# csa_sid_v1_0b.net
KiCad netlist of a schematic drawn in EAGLE
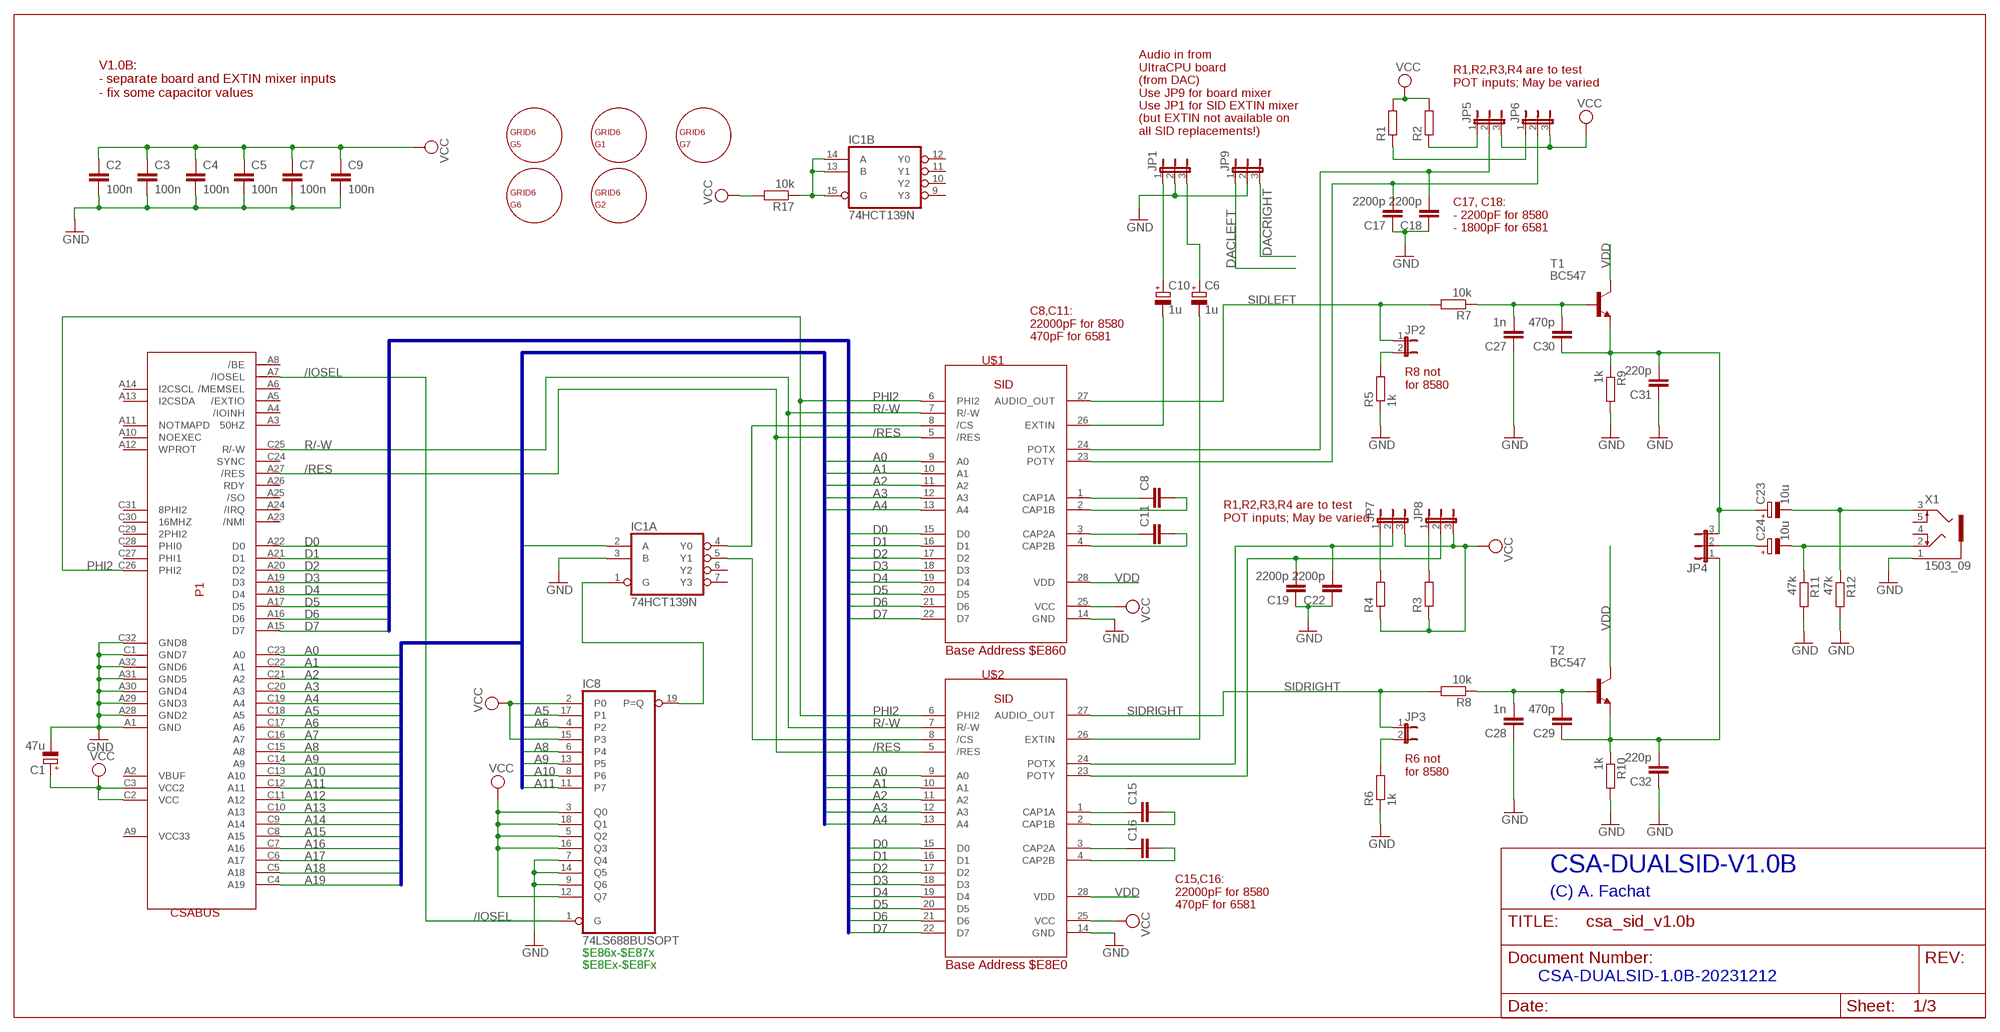
[diagram p0: schematic, sheet 1]
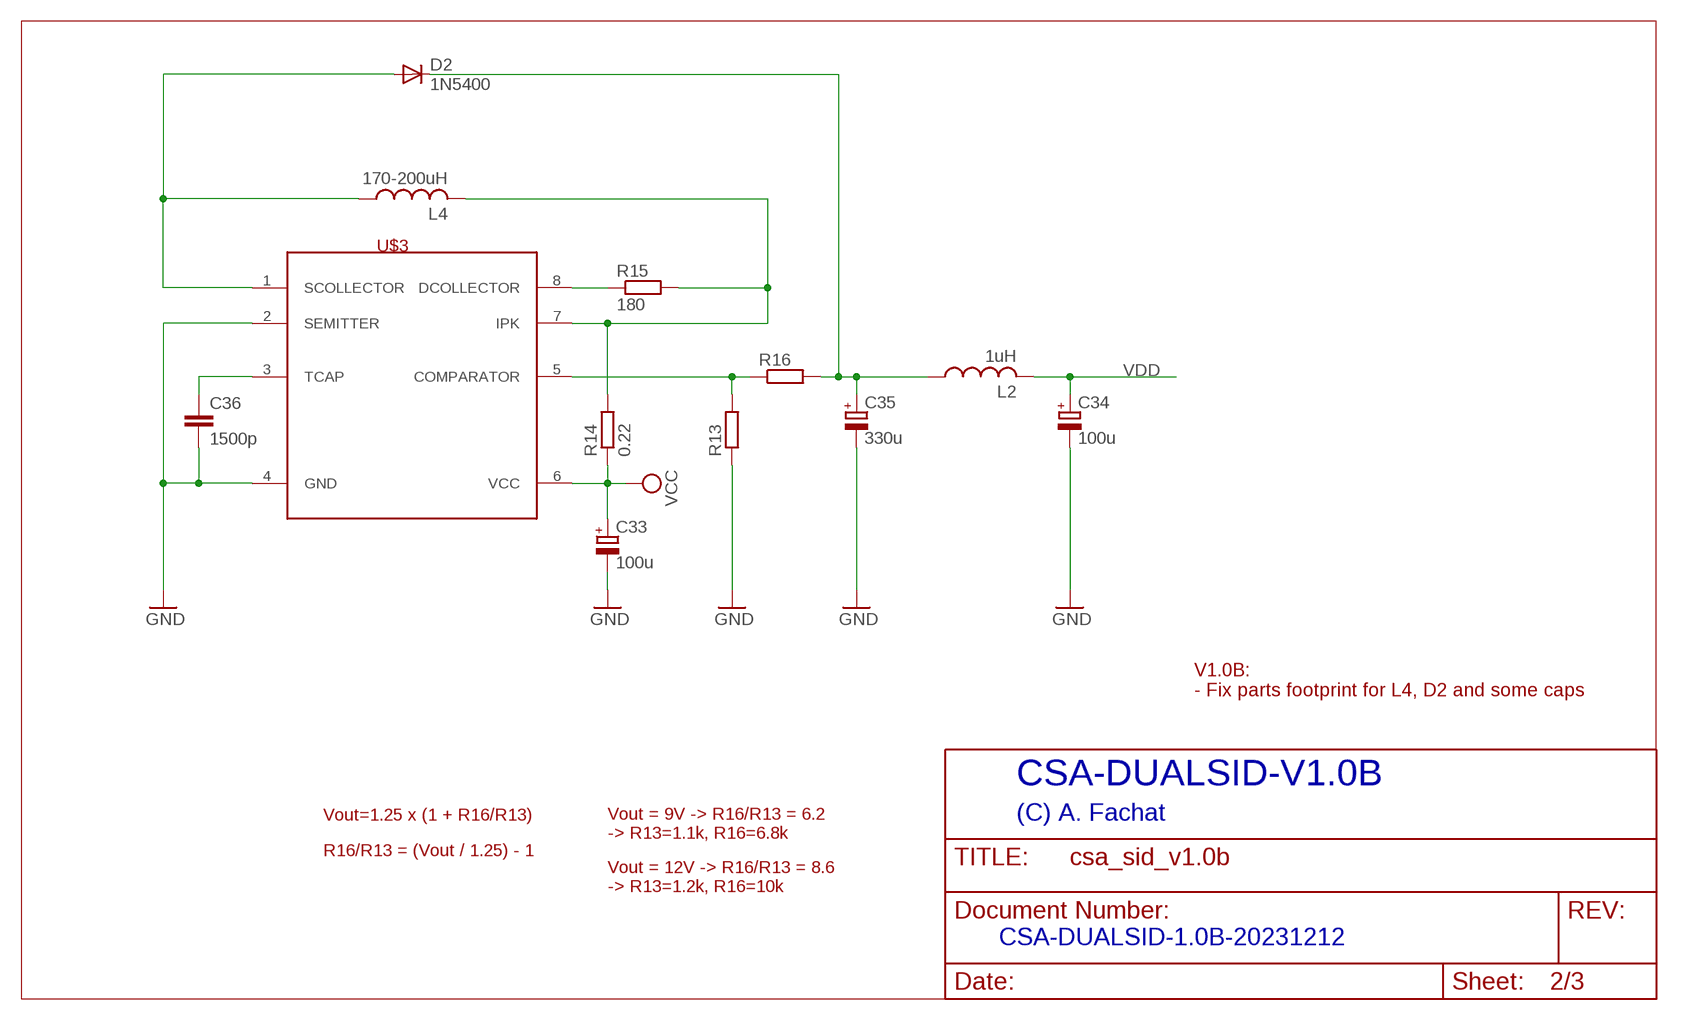
[diagram p1: schematic, sheet 2]
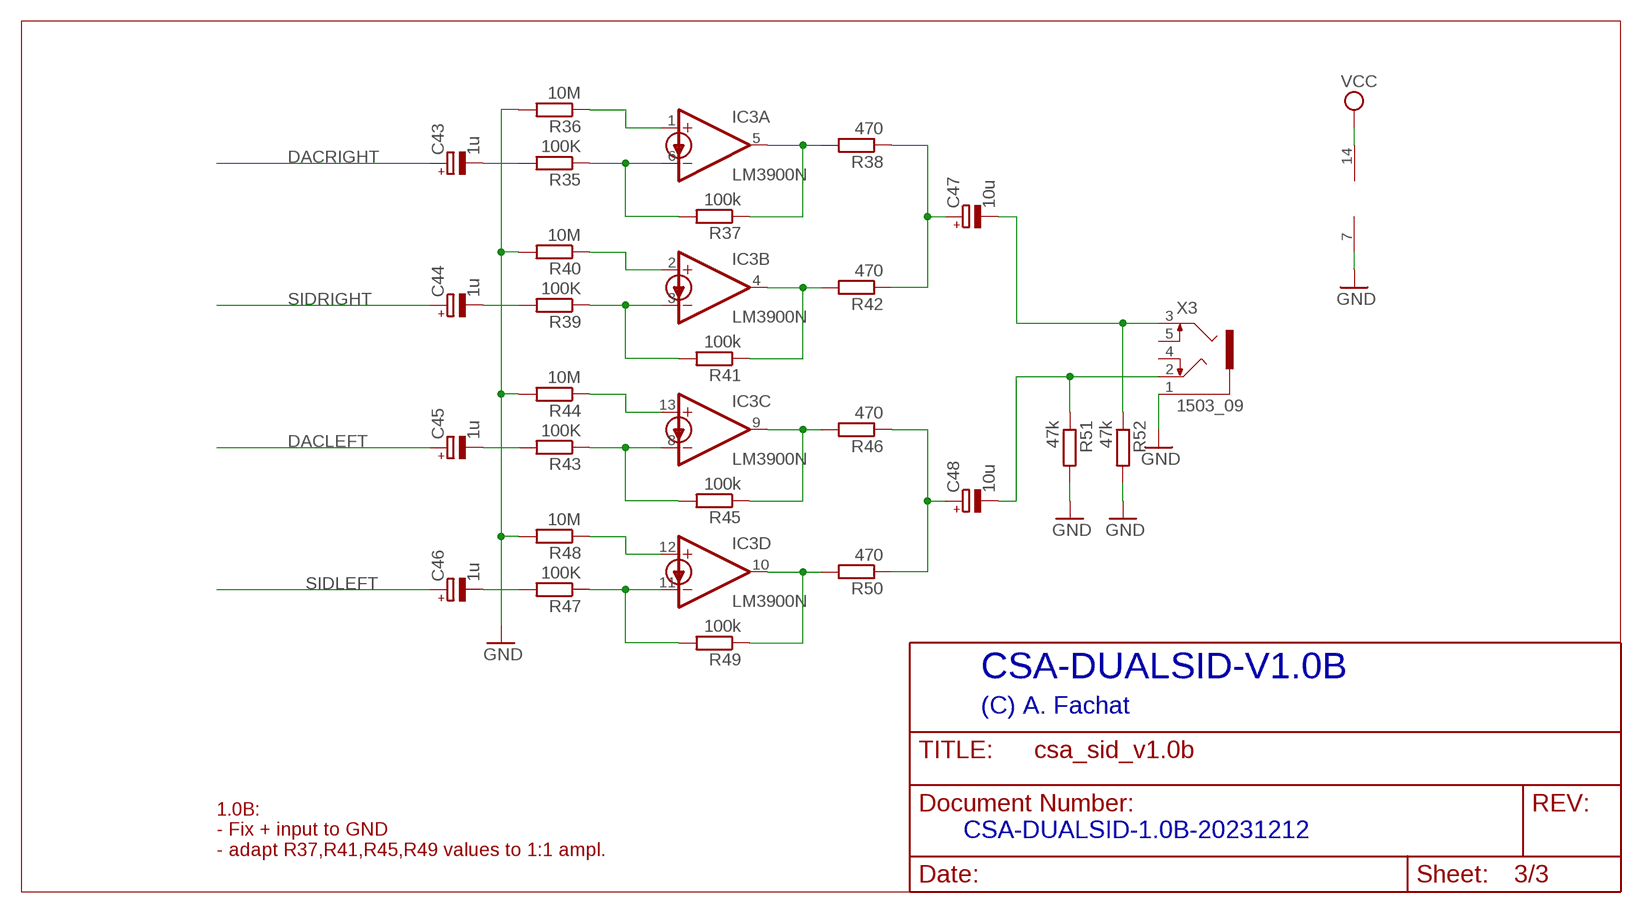
[diagram p2: schematic, sheet 3]

(export (version "E")
  (design (tool "Eeschema 10.0.6"))
  (components
    (comp (ref "C33")
      (value "100u")
      (footprint "eagle-import:E2,5-7")
      (libsource (lib "eagle-import") (part "CPOL-EUE2.5-7"))
    )
    (comp (ref "C34")
      (value "100u")
      (footprint "eagle-import:E2,5-7")
      (libsource (lib "eagle-import") (part "CPOL-EUE2.5-7"))
    )
    (comp (ref "C35")
      (value "330u")
      (footprint "eagle-import:E2,5-7")
      (libsource (lib "eagle-import") (part "CPOL-EUE2.5-7"))
    )
    (comp (ref "C36")
      (value "1500p")
      (footprint "eagle-import:C025-024X044")
      (libsource (lib "eagle-import") (part "C-EU025-024X044"))
    )
    (comp (ref "D2")
      (value "1N5400")
      (footprint "eagle-import:DO201-15")
      (libsource (lib "eagle-import") (part "1N5400"))
    )
    (comp (ref "L2")
      (value "1uH")
      (footprint "eagle-import:0204_7")
      (libsource (lib "eagle-import") (part "L-US0204/7"))
    )
    (comp (ref "L4")
      (value "170-200uH")
      (footprint "eagle-import:TJ4-U2")
      (libsource (lib "eagle-import") (part "L-USTJ4-U2"))
    )
    (comp (ref "R13")
      (value "R-EU_0204/7")
      (footprint "eagle-import:0204_7")
      (libsource (lib "eagle-import") (part "R-EU_0204/7"))
    )
    (comp (ref "R14")
      (value "0.22")
      (footprint "eagle-import:0204_7")
      (libsource (lib "eagle-import") (part "R-EU_0204/7"))
    )
    (comp (ref "R15")
      (value "180")
      (footprint "eagle-import:0204_7")
      (libsource (lib "eagle-import") (part "R-EU_0204/7"))
    )
    (comp (ref "R16")
      (value "R-EU_0204/7")
      (footprint "eagle-import:0204_7")
      (libsource (lib "eagle-import") (part "R-EU_0204/7"))
    )
    (comp (ref "U$3")
      (value "MC34063A")
      (footprint "eagle-import:DIL08")
      (libsource (lib "eagle-import") (part "MC34063A"))
    )
    (comp (ref "C1")
      (value "47u")
      (footprint "eagle-import:E2,5-7")
      (libsource (lib "eagle-import") (part "CPOL-EUE2.5-7"))
    )
    (comp (ref "C2")
      (value "100n")
      (footprint "eagle-import:C025-025X050")
      (libsource (lib "eagle-import") (part "C-EU025-025X050"))
    )
    (comp (ref "C3")
      (value "100n")
      (footprint "eagle-import:C025-025X050")
      (libsource (lib "eagle-import") (part "C-EU025-025X050"))
    )
    (comp (ref "C4")
      (value "100n")
      (footprint "eagle-import:C025-025X050")
      (libsource (lib "eagle-import") (part "C-EU025-025X050"))
    )
    (comp (ref "C5")
      (value "100n")
      (footprint "eagle-import:C025-025X050")
      (libsource (lib "eagle-import") (part "C-EU025-025X050"))
    )
    (comp (ref "C6")
      (value "1u")
      (footprint "eagle-import:E2-5")
      (libsource (lib "eagle-import") (part "CPOL-EUE2-5"))
    )
    (comp (ref "C7")
      (value "100n")
      (footprint "eagle-import:C025-025X050")
      (libsource (lib "eagle-import") (part "C-EU025-025X050"))
    )
    (comp (ref "C8")
      (value "C-EU025-025X050")
      (footprint "eagle-import:C025-025X050")
      (libsource (lib "eagle-import") (part "C-EU025-025X050"))
    )
    (comp (ref "C9")
      (value "100n")
      (footprint "eagle-import:C025-025X050")
      (libsource (lib "eagle-import") (part "C-EU025-025X050"))
    )
    (comp (ref "C10")
      (value "1u")
      (footprint "eagle-import:E2-5")
      (libsource (lib "eagle-import") (part "CPOL-EUE2-5"))
    )
    (comp (ref "C11")
      (value "C-EU025-025X050")
      (footprint "eagle-import:C025-025X050")
      (libsource (lib "eagle-import") (part "C-EU025-025X050"))
    )
    (comp (ref "C15")
      (value "C-EU025-025X050")
      (footprint "eagle-import:C025-025X050")
      (libsource (lib "eagle-import") (part "C-EU025-025X050"))
    )
    (comp (ref "C16")
      (value "C-EU025-025X050")
      (footprint "eagle-import:C025-025X050")
      (libsource (lib "eagle-import") (part "C-EU025-025X050"))
    )
    (comp (ref "C17")
      (value "2200p")
      (footprint "eagle-import:C025-025X050")
      (libsource (lib "eagle-import") (part "C-EU025-025X050"))
    )
    (comp (ref "C18")
      (value "2200p")
      (footprint "eagle-import:C025-025X050")
      (libsource (lib "eagle-import") (part "C-EU025-025X050"))
    )
    (comp (ref "C19")
      (value "2200p")
      (footprint "eagle-import:C025-025X050")
      (libsource (lib "eagle-import") (part "C-EU025-025X050"))
    )
    (comp (ref "C22")
      (value "2200p")
      (footprint "eagle-import:C025-025X050")
      (libsource (lib "eagle-import") (part "C-EU025-025X050"))
    )
    (comp (ref "C23")
      (value "10u")
      (footprint "eagle-import:E2-5")
      (libsource (lib "eagle-import") (part "CPOL-EUE2-5"))
    )
    (comp (ref "C24")
      (value "10u")
      (footprint "eagle-import:E2-5")
      (libsource (lib "eagle-import") (part "CPOL-EUE2-5"))
    )
    (comp (ref "C27")
      (value "1n")
      (footprint "eagle-import:C025-025X050")
      (libsource (lib "eagle-import") (part "C-EU025-025X050"))
    )
    (comp (ref "C28")
      (value "1n")
      (footprint "eagle-import:C025-025X050")
      (libsource (lib "eagle-import") (part "C-EU025-025X050"))
    )
    (comp (ref "C29")
      (value "470p")
      (footprint "eagle-import:C025-025X050")
      (libsource (lib "eagle-import") (part "C-EU025-025X050"))
    )
    (comp (ref "C30")
      (value "470p")
      (footprint "eagle-import:C025-025X050")
      (libsource (lib "eagle-import") (part "C-EU025-025X050"))
    )
    (comp (ref "C31")
      (value "220p")
      (footprint "eagle-import:C025-025X050")
      (libsource (lib "eagle-import") (part "C-EU025-025X050"))
    )
    (comp (ref "C32")
      (value "220p")
      (footprint "eagle-import:C025-025X050")
      (libsource (lib "eagle-import") (part "C-EU025-025X050"))
    )
    (comp (ref "G1")
      (value "GRID6")
      (footprint "eagle-import:GRID6")
      (libsource (lib "eagle-import") (part "GRID6"))
    )
    (comp (ref "G2")
      (value "GRID6")
      (footprint "eagle-import:GRID6")
      (libsource (lib "eagle-import") (part "GRID6"))
    )
    (comp (ref "G5")
      (value "GRID6")
      (footprint "eagle-import:GRID6")
      (libsource (lib "eagle-import") (part "GRID6"))
    )
    (comp (ref "G6")
      (value "GRID6")
      (footprint "eagle-import:GRID6")
      (libsource (lib "eagle-import") (part "GRID6"))
    )
    (comp (ref "G7")
      (value "GRID6")
      (footprint "eagle-import:GRID6")
      (libsource (lib "eagle-import") (part "GRID6"))
    )
    (comp (ref "IC1")
      (value "74HCT139N")
      (footprint "eagle-import:DIL16")
      (libsource (lib "eagle-import") (part "74139NHCT"))
    )
    (comp (ref "IC8")
      (value "74LS688BUSOPT")
      (footprint "eagle-import:DIL20")
      (libsource (lib "eagle-import") (part "74LS688BUSOPT"))
    )
    (comp (ref "JP1")
      (value "JP2E")
      (footprint "eagle-import:JP2")
      (libsource (lib "eagle-import") (part "JP2E"))
    )
    (comp (ref "JP2")
      (value "JP1E")
      (footprint "eagle-import:JP1")
      (libsource (lib "eagle-import") (part "JP1E"))
    )
    (comp (ref "JP3")
      (value "JP1E")
      (footprint "eagle-import:JP1")
      (libsource (lib "eagle-import") (part "JP1E"))
    )
    (comp (ref "JP4")
      (value "JP2E")
      (footprint "eagle-import:JP2")
      (libsource (lib "eagle-import") (part "JP2E"))
    )
    (comp (ref "JP5")
      (value "JP2E")
      (footprint "eagle-import:JP2")
      (libsource (lib "eagle-import") (part "JP2E"))
    )
    (comp (ref "JP6")
      (value "JP2E")
      (footprint "eagle-import:JP2")
      (libsource (lib "eagle-import") (part "JP2E"))
    )
    (comp (ref "JP7")
      (value "JP2E")
      (footprint "eagle-import:JP2")
      (libsource (lib "eagle-import") (part "JP2E"))
    )
    (comp (ref "JP8")
      (value "JP2E")
      (footprint "eagle-import:JP2")
      (libsource (lib "eagle-import") (part "JP2E"))
    )
    (comp (ref "JP9")
      (value "JP2E")
      (footprint "eagle-import:JP2")
      (libsource (lib "eagle-import") (part "JP2E"))
    )
    (comp (ref "P1")
      (value "CSABUS")
      (footprint "eagle-import:CSABUS")
      (libsource (lib "eagle-import") (part "CSABUS"))
    )
    (comp (ref "R1")
      (value "R-EU_0204/7")
      (footprint "eagle-import:0204_7")
      (libsource (lib "eagle-import") (part "R-EU_0204/7"))
    )
    (comp (ref "R2")
      (value "R-EU_0204/7")
      (footprint "eagle-import:0204_7")
      (libsource (lib "eagle-import") (part "R-EU_0204/7"))
    )
    (comp (ref "R3")
      (value "R-EU_0204/7")
      (footprint "eagle-import:0204_7")
      (libsource (lib "eagle-import") (part "R-EU_0204/7"))
    )
    (comp (ref "R4")
      (value "R-EU_0204/7")
      (footprint "eagle-import:0204_7")
      (libsource (lib "eagle-import") (part "R-EU_0204/7"))
    )
    (comp (ref "R5")
      (value "1k")
      (footprint "eagle-import:0204_7")
      (libsource (lib "eagle-import") (part "R-EU_0204/7"))
    )
    (comp (ref "R6")
      (value "1k")
      (footprint "eagle-import:0204_7")
      (libsource (lib "eagle-import") (part "R-EU_0204/7"))
    )
    (comp (ref "R7")
      (value "10k")
      (footprint "eagle-import:0204_7")
      (libsource (lib "eagle-import") (part "R-EU_0204/7"))
    )
    (comp (ref "R8")
      (value "10k")
      (footprint "eagle-import:0204_7")
      (libsource (lib "eagle-import") (part "R-EU_0204/7"))
    )
    (comp (ref "R9")
      (value "1k")
      (footprint "eagle-import:0204_7")
      (libsource (lib "eagle-import") (part "R-EU_0204/7"))
    )
    (comp (ref "R10")
      (value "1k")
      (footprint "eagle-import:0204_7")
      (libsource (lib "eagle-import") (part "R-EU_0204/7"))
    )
    (comp (ref "R11")
      (value "47k")
      (footprint "eagle-import:0204_7")
      (libsource (lib "eagle-import") (part "R-EU_0204/7"))
    )
    (comp (ref "R12")
      (value "47k")
      (footprint "eagle-import:0204_7")
      (libsource (lib "eagle-import") (part "R-EU_0204/7"))
    )
    (comp (ref "R17")
      (value "10k")
      (footprint "eagle-import:0204_7")
      (libsource (lib "eagle-import") (part "R-EU_0204/7"))
    )
    (comp (ref "T1")
      (value "BC547")
      (footprint "eagle-import:TO92")
      (libsource (lib "eagle-import") (part "BC547"))
    )
    (comp (ref "T2")
      (value "BC547")
      (footprint "eagle-import:TO92")
      (libsource (lib "eagle-import") (part "BC547"))
    )
    (comp (ref "U$1")
      (value "SID")
      (footprint "eagle-import:DIL28")
      (libsource (lib "eagle-import") (part "SID"))
    )
    (comp (ref "U$2")
      (value "SID")
      (footprint "eagle-import:DIL28")
      (libsource (lib "eagle-import") (part "SID"))
    )
    (comp (ref "X1")
      (value "1503_09")
      (footprint "eagle-import:1503_09")
      (libsource (lib "eagle-import") (part "1503_09"))
    )
    (comp (ref "C43")
      (value "1u")
      (footprint "eagle-import:E2-5")
      (libsource (lib "eagle-import") (part "CPOL-EUE2-5"))
    )
    (comp (ref "C44")
      (value "1u")
      (footprint "eagle-import:E2-5")
      (libsource (lib "eagle-import") (part "CPOL-EUE2-5"))
    )
    (comp (ref "C45")
      (value "1u")
      (footprint "eagle-import:E2-5")
      (libsource (lib "eagle-import") (part "CPOL-EUE2-5"))
    )
    (comp (ref "C46")
      (value "1u")
      (footprint "eagle-import:E2-5")
      (libsource (lib "eagle-import") (part "CPOL-EUE2-5"))
    )
    (comp (ref "C47")
      (value "10u")
      (footprint "eagle-import:E2-5")
      (libsource (lib "eagle-import") (part "CPOL-EUE2-5"))
    )
    (comp (ref "C48")
      (value "10u")
      (footprint "eagle-import:E2-5")
      (libsource (lib "eagle-import") (part "CPOL-EUE2-5"))
    )
    (comp (ref "IC3")
      (value "LM3900N")
      (footprint "eagle-import:DIL14")
      (libsource (lib "eagle-import") (part "LM3900N"))
    )
    (comp (ref "R35")
      (value "100K")
      (footprint "eagle-import:0204_7")
      (libsource (lib "eagle-import") (part "R-EU_0204/7"))
    )
    (comp (ref "R36")
      (value "10M")
      (footprint "eagle-import:0204_7")
      (libsource (lib "eagle-import") (part "R-EU_0204/7"))
    )
    (comp (ref "R37")
      (value "100k")
      (footprint "eagle-import:0204_7")
      (libsource (lib "eagle-import") (part "R-EU_0204/7"))
    )
    (comp (ref "R38")
      (value "470")
      (footprint "eagle-import:0204_7")
      (libsource (lib "eagle-import") (part "R-EU_0204/7"))
    )
    (comp (ref "R39")
      (value "100K")
      (footprint "eagle-import:0204_7")
      (libsource (lib "eagle-import") (part "R-EU_0204/7"))
    )
    (comp (ref "R40")
      (value "10M")
      (footprint "eagle-import:0204_7")
      (libsource (lib "eagle-import") (part "R-EU_0204/7"))
    )
    (comp (ref "R41")
      (value "100k")
      (footprint "eagle-import:0204_7")
      (libsource (lib "eagle-import") (part "R-EU_0204/7"))
    )
    (comp (ref "R42")
      (value "470")
      (footprint "eagle-import:0204_7")
      (libsource (lib "eagle-import") (part "R-EU_0204/7"))
    )
    (comp (ref "R43")
      (value "100K")
      (footprint "eagle-import:0204_7")
      (libsource (lib "eagle-import") (part "R-EU_0204/7"))
    )
    (comp (ref "R44")
      (value "10M")
      (footprint "eagle-import:0204_7")
      (libsource (lib "eagle-import") (part "R-EU_0204/7"))
    )
    (comp (ref "R45")
      (value "100k")
      (footprint "eagle-import:0204_7")
      (libsource (lib "eagle-import") (part "R-EU_0204/7"))
    )
    (comp (ref "R46")
      (value "470")
      (footprint "eagle-import:0204_7")
      (libsource (lib "eagle-import") (part "R-EU_0204/7"))
    )
    (comp (ref "R47")
      (value "100K")
      (footprint "eagle-import:0204_7")
      (libsource (lib "eagle-import") (part "R-EU_0204/7"))
    )
    (comp (ref "R48")
      (value "10M")
      (footprint "eagle-import:0204_7")
      (libsource (lib "eagle-import") (part "R-EU_0204/7"))
    )
    (comp (ref "R49")
      (value "100k")
      (footprint "eagle-import:0204_7")
      (libsource (lib "eagle-import") (part "R-EU_0204/7"))
    )
    (comp (ref "R50")
      (value "470")
      (footprint "eagle-import:0204_7")
      (libsource (lib "eagle-import") (part "R-EU_0204/7"))
    )
    (comp (ref "R51")
      (value "47k")
      (footprint "eagle-import:0204_7")
      (libsource (lib "eagle-import") (part "R-EU_0204/7"))
    )
    (comp (ref "R52")
      (value "47k")
      (footprint "eagle-import:0204_7")
      (libsource (lib "eagle-import") (part "R-EU_0204/7"))
    )
    (comp (ref "X3")
      (value "1503_09")
      (footprint "eagle-import:1503_09")
      (libsource (lib "eagle-import") (part "1503_09"))
    )
  )
  (nets
    (net (code "1") (name "A0") (class "Default")
      (node (ref "P1") (pin "C23") (pinfunction "A0_C23") (pintype "bidirectional"))
      (node (ref "U$1") (pin "9") (pinfunction "A0_9") (pintype "bidirectional"))
      (node (ref "U$2") (pin "9") (pinfunction "A0_9") (pintype "bidirectional"))
    )
    (net (code "2") (name "A1") (class "Default")
      (node (ref "P1") (pin "C22") (pinfunction "A1_C22") (pintype "bidirectional"))
      (node (ref "U$1") (pin "10") (pinfunction "A1_10") (pintype "bidirectional"))
      (node (ref "U$2") (pin "10") (pinfunction "A1_10") (pintype "bidirectional"))
    )
    (net (code "3") (name "A2") (class "Default")
      (node (ref "P1") (pin "C21") (pinfunction "A2_C21") (pintype "bidirectional"))
      (node (ref "U$1") (pin "11") (pinfunction "A2_11") (pintype "bidirectional"))
      (node (ref "U$2") (pin "11") (pinfunction "A2_11") (pintype "bidirectional"))
    )
    (net (code "4") (name "A3") (class "Default")
      (node (ref "P1") (pin "C20") (pinfunction "A3_C20") (pintype "bidirectional"))
      (node (ref "U$1") (pin "12") (pinfunction "A3_12") (pintype "bidirectional"))
      (node (ref "U$2") (pin "12") (pinfunction "A3_12") (pintype "bidirectional"))
    )
    (net (code "5") (name "A4") (class "Default")
      (node (ref "P1") (pin "C19") (pinfunction "A4_C19") (pintype "bidirectional"))
      (node (ref "U$1") (pin "13") (pinfunction "A4_13") (pintype "bidirectional"))
      (node (ref "U$2") (pin "13") (pinfunction "A4_13") (pintype "bidirectional"))
    )
    (net (code "6") (name "A5") (class "Default")
      (node (ref "IC8") (pin "17") (pinfunction "P1_17") (pintype "input"))
      (node (ref "P1") (pin "C18") (pinfunction "A5_C18") (pintype "bidirectional"))
    )
    (net (code "7") (name "A6") (class "Default")
      (node (ref "IC8") (pin "4") (pinfunction "P2_4") (pintype "input"))
      (node (ref "P1") (pin "C17") (pinfunction "A6_C17") (pintype "bidirectional"))
    )
    (net (code "8") (name "A7") (class "Default")
      (node (ref "IC1") (pin "2") (pinfunction "A_2") (pintype "input"))
      (node (ref "P1") (pin "C16") (pinfunction "A7_C16") (pintype "bidirectional"))
    )
    (net (code "9") (name "A8") (class "Default")
      (node (ref "IC8") (pin "6") (pinfunction "P4_6") (pintype "input"))
      (node (ref "P1") (pin "C15") (pinfunction "A8_C15") (pintype "bidirectional"))
    )
    (net (code "10") (name "A9") (class "Default")
      (node (ref "IC8") (pin "13") (pinfunction "P5_13") (pintype "input"))
      (node (ref "P1") (pin "C14") (pinfunction "A9_C14") (pintype "bidirectional"))
    )
    (net (code "11") (name "A10") (class "Default")
      (node (ref "IC8") (pin "8") (pinfunction "P6_8") (pintype "input"))
      (node (ref "P1") (pin "C13") (pinfunction "A10_C13") (pintype "bidirectional"))
    )
    (net (code "12") (name "A11") (class "Default")
      (node (ref "IC8") (pin "11") (pinfunction "P7_11") (pintype "input"))
      (node (ref "P1") (pin "C12") (pinfunction "A11_C12") (pintype "bidirectional"))
    )
    (net (code "13") (name "A12") (class "Default")
      (node (ref "P1") (pin "C11") (pinfunction "A12_C11") (pintype "bidirectional"))
    )
    (net (code "14") (name "A13") (class "Default")
      (node (ref "P1") (pin "C10") (pinfunction "A13_C10") (pintype "bidirectional"))
    )
    (net (code "15") (name "A14") (class "Default")
      (node (ref "P1") (pin "C9") (pinfunction "A14_C9") (pintype "bidirectional"))
    )
    (net (code "16") (name "A15") (class "Default")
      (node (ref "P1") (pin "C8") (pinfunction "A15_C8") (pintype "bidirectional"))
    )
    (net (code "17") (name "A16") (class "Default")
      (node (ref "P1") (pin "C7") (pinfunction "A16_C7") (pintype "bidirectional"))
    )
    (net (code "18") (name "A17") (class "Default")
      (node (ref "P1") (pin "C6") (pinfunction "A17_C6") (pintype "bidirectional"))
    )
    (net (code "19") (name "A18") (class "Default")
      (node (ref "P1") (pin "C5") (pinfunction "A18_C5") (pintype "bidirectional"))
    )
    (net (code "20") (name "A19") (class "Default")
      (node (ref "P1") (pin "C4") (pinfunction "A19_C4") (pintype "bidirectional"))
    )
    (net (code "21") (name "D0") (class "Default")
      (node (ref "P1") (pin "A22") (pinfunction "D0_A22") (pintype "bidirectional"))
      (node (ref "U$1") (pin "15") (pinfunction "D0_15") (pintype "bidirectional"))
      (node (ref "U$2") (pin "15") (pinfunction "D0_15") (pintype "bidirectional"))
    )
    (net (code "22") (name "D1") (class "Default")
      (node (ref "P1") (pin "A21") (pinfunction "D1_A21") (pintype "bidirectional"))
      (node (ref "U$1") (pin "16") (pinfunction "D1_16") (pintype "bidirectional"))
      (node (ref "U$2") (pin "16") (pinfunction "D1_16") (pintype "bidirectional"))
    )
    (net (code "23") (name "D2") (class "Default")
      (node (ref "P1") (pin "A20") (pinfunction "D2_A20") (pintype "bidirectional"))
      (node (ref "U$1") (pin "17") (pinfunction "D2_17") (pintype "bidirectional"))
      (node (ref "U$2") (pin "17") (pinfunction "D2_17") (pintype "bidirectional"))
    )
    (net (code "24") (name "D3") (class "Default")
      (node (ref "P1") (pin "A19") (pinfunction "D3_A19") (pintype "bidirectional"))
      (node (ref "U$1") (pin "18") (pinfunction "D3_18") (pintype "bidirectional"))
      (node (ref "U$2") (pin "18") (pinfunction "D3_18") (pintype "bidirectional"))
    )
    (net (code "25") (name "D4") (class "Default")
      (node (ref "P1") (pin "A18") (pinfunction "D4_A18") (pintype "bidirectional"))
      (node (ref "U$1") (pin "19") (pinfunction "D4_19") (pintype "bidirectional"))
      (node (ref "U$2") (pin "19") (pinfunction "D4_19") (pintype "bidirectional"))
    )
    (net (code "26") (name "D5") (class "Default")
      (node (ref "P1") (pin "A17") (pinfunction "D5_A17") (pintype "bidirectional"))
      (node (ref "U$1") (pin "20") (pinfunction "D5_20") (pintype "bidirectional"))
      (node (ref "U$2") (pin "20") (pinfunction "D5_20") (pintype "bidirectional"))
    )
    (net (code "27") (name "D6") (class "Default")
      (node (ref "P1") (pin "A16") (pinfunction "D6_A16") (pintype "bidirectional"))
      (node (ref "U$1") (pin "21") (pinfunction "D6_21") (pintype "bidirectional"))
      (node (ref "U$2") (pin "21") (pinfunction "D6_21") (pintype "bidirectional"))
    )
    (net (code "28") (name "D7") (class "Default")
      (node (ref "P1") (pin "A15") (pinfunction "D7_A15") (pintype "bidirectional"))
      (node (ref "U$1") (pin "22") (pinfunction "D7_22") (pintype "bidirectional"))
      (node (ref "U$2") (pin "22") (pinfunction "D7_22") (pintype "bidirectional"))
    )
    (net (code "29") (name "DACLEFT") (class "Default")
      (node (ref "C45") (pin "+") (pinfunction "+_+") (pintype "passive"))
      (node (ref "JP9") (pin "1") (pinfunction "1_1") (pintype "passive"))
    )
    (net (code "30") (name "DACRIGHT") (class "Default")
      (node (ref "C43") (pin "+") (pinfunction "+_+") (pintype "passive"))
      (node (ref "JP9") (pin "3") (pinfunction "3_3") (pintype "passive"))
    )
    (net (code "31") (name "GND") (class "Default")
      (node (ref "C1") (pin "-") (pinfunction "-_-") (pintype "passive"))
      (node (ref "C17") (pin "1") (pinfunction "1_1") (pintype "passive"))
      (node (ref "C18") (pin "1") (pinfunction "1_1") (pintype "passive"))
      (node (ref "C19") (pin "1") (pinfunction "1_1") (pintype "passive"))
      (node (ref "C2") (pin "2") (pinfunction "2_2") (pintype "passive"))
      (node (ref "C22") (pin "1") (pinfunction "1_1") (pintype "passive"))
      (node (ref "C27") (pin "1") (pinfunction "1_1") (pintype "passive"))
      (node (ref "C28") (pin "1") (pinfunction "1_1") (pintype "passive"))
      (node (ref "C3") (pin "2") (pinfunction "2_2") (pintype "passive"))
      (node (ref "C31") (pin "1") (pinfunction "1_1") (pintype "passive"))
      (node (ref "C32") (pin "1") (pinfunction "1_1") (pintype "passive"))
      (node (ref "C33") (pin "-") (pinfunction "-_-") (pintype "passive"))
      (node (ref "C34") (pin "-") (pinfunction "-_-") (pintype "passive"))
      (node (ref "C35") (pin "-") (pinfunction "-_-") (pintype "passive"))
      (node (ref "C36") (pin "2") (pinfunction "2_2") (pintype "passive"))
      (node (ref "C4") (pin "2") (pinfunction "2_2") (pintype "passive"))
      (node (ref "C5") (pin "2") (pinfunction "2_2") (pintype "passive"))
      (node (ref "C7") (pin "2") (pinfunction "2_2") (pintype "passive"))
      (node (ref "C9") (pin "2") (pinfunction "2_2") (pintype "passive"))
      (node (ref "IC1") (pin "3") (pinfunction "B_3") (pintype "input"))
      (node (ref "IC3") (pin "7") (pinfunction "GND_7") (pintype "power_in"))
      (node (ref "IC8") (pin "14") (pinfunction "Q5_14") (pintype "input"))
      (node (ref "IC8") (pin "7") (pinfunction "Q4_7") (pintype "input"))
      (node (ref "IC8") (pin "9") (pinfunction "Q6_9") (pintype "input"))
      (node (ref "JP1") (pin "2") (pinfunction "2_2") (pintype "passive"))
      (node (ref "JP9") (pin "2") (pinfunction "2_2") (pintype "passive"))
      (node (ref "P1") (pin "A1") (pinfunction "GND_A1") (pintype "bidirectional"))
      (node (ref "P1") (pin "A28") (pinfunction "GND2_A28") (pintype "bidirectional"))
      (node (ref "P1") (pin "A29") (pinfunction "GND3_A29") (pintype "bidirectional"))
      (node (ref "P1") (pin "A30") (pinfunction "GND4_A30") (pintype "bidirectional"))
      (node (ref "P1") (pin "A31") (pinfunction "GND5_A31") (pintype "bidirectional"))
      (node (ref "P1") (pin "A32") (pinfunction "GND6_A32") (pintype "bidirectional"))
      (node (ref "P1") (pin "C1") (pinfunction "GND7_C1") (pintype "bidirectional"))
      (node (ref "P1") (pin "C32") (pinfunction "GND8_C32") (pintype "bidirectional"))
      (node (ref "R10") (pin "2") (pinfunction "2_2") (pintype "passive"))
      (node (ref "R11") (pin "2") (pinfunction "2_2") (pintype "passive"))
      (node (ref "R12") (pin "2") (pinfunction "2_2") (pintype "passive"))
      (node (ref "R13") (pin "1") (pinfunction "1_1") (pintype "passive"))
      (node (ref "R36") (pin "2") (pinfunction "2_2") (pintype "passive"))
      (node (ref "R40") (pin "2") (pinfunction "2_2") (pintype "passive"))
      (node (ref "R44") (pin "2") (pinfunction "2_2") (pintype "passive"))
      (node (ref "R48") (pin "2") (pinfunction "2_2") (pintype "passive"))
      (node (ref "R5") (pin "1") (pinfunction "1_1") (pintype "passive"))
      (node (ref "R51") (pin "2") (pinfunction "2_2") (pintype "passive"))
      (node (ref "R52") (pin "2") (pinfunction "2_2") (pintype "passive"))
      (node (ref "R6") (pin "1") (pinfunction "1_1") (pintype "passive"))
      (node (ref "R9") (pin "2") (pinfunction "2_2") (pintype "passive"))
      (node (ref "U$1") (pin "14") (pinfunction "GND_14") (pintype "bidirectional"))
      (node (ref "U$2") (pin "14") (pinfunction "GND_14") (pintype "bidirectional"))
      (node (ref "U$3") (pin "2") (pinfunction "SEMITTER_2") (pintype "bidirectional"))
      (node (ref "U$3") (pin "4") (pinfunction "GND_4") (pintype "bidirectional"))
      (node (ref "X1") (pin "1") (pinfunction "1_1") (pintype "passive"))
      (node (ref "X3") (pin "1") (pinfunction "1_1") (pintype "passive"))
    )
    (net (code "32") (name "Net-(C6-Pad+)") (class "Default")
      (node (ref "C6") (pin "+") (pinfunction "+_+") (pintype "passive"))
      (node (ref "JP1") (pin "3") (pinfunction "3_3") (pintype "passive"))
    )
    (net (code "33") (name "Net-(C10-Pad+)") (class "Default")
      (node (ref "C10") (pin "+") (pinfunction "+_+") (pintype "passive"))
      (node (ref "JP1") (pin "1") (pinfunction "1_1") (pintype "passive"))
    )
    (net (code "34") (name "Net-(C23-Pad-)") (class "Default")
      (node (ref "C23") (pin "-") (pinfunction "-_-") (pintype "passive"))
      (node (ref "R12") (pin "1") (pinfunction "1_1") (pintype "passive"))
      (node (ref "X1") (pin "3") (pinfunction "3_3") (pintype "passive"))
    )
    (net (code "35") (name "Net-(C24-Pad+)") (class "Default")
      (node (ref "C24") (pin "+") (pinfunction "+_+") (pintype "passive"))
      (node (ref "JP4") (pin "2") (pinfunction "2_2") (pintype "passive"))
    )
    (net (code "36") (name "Net-(C24-Pad-)") (class "Default")
      (node (ref "C24") (pin "-") (pinfunction "-_-") (pintype "passive"))
      (node (ref "R11") (pin "1") (pinfunction "1_1") (pintype "passive"))
      (node (ref "X1") (pin "2") (pinfunction "2_2") (pintype "passive"))
    )
    (net (code "37") (name "Net-(C35-Pad+)") (class "Default")
      (node (ref "C35") (pin "+") (pinfunction "+_+") (pintype "passive"))
      (node (ref "D2") (pin "C") (pinfunction "C_C") (pintype "passive"))
      (node (ref "L2") (pin "1") (pinfunction "1_1") (pintype "passive"))
      (node (ref "R16") (pin "2") (pinfunction "2_2") (pintype "passive"))
    )
    (net (code "38") (name "Net-(C43-Pad-)") (class "Default")
      (node (ref "C43") (pin "-") (pinfunction "-_-") (pintype "passive"))
      (node (ref "R35") (pin "2") (pinfunction "2_2") (pintype "passive"))
    )
    (net (code "39") (name "Net-(C44-Pad-)") (class "Default")
      (node (ref "C44") (pin "-") (pinfunction "-_-") (pintype "passive"))
      (node (ref "R39") (pin "2") (pinfunction "2_2") (pintype "passive"))
    )
    (net (code "40") (name "Net-(C45-Pad-)") (class "Default")
      (node (ref "C45") (pin "-") (pinfunction "-_-") (pintype "passive"))
      (node (ref "R43") (pin "2") (pinfunction "2_2") (pintype "passive"))
    )
    (net (code "41") (name "Net-(C46-Pad-)") (class "Default")
      (node (ref "C46") (pin "-") (pinfunction "-_-") (pintype "passive"))
      (node (ref "R47") (pin "2") (pinfunction "2_2") (pintype "passive"))
    )
    (net (code "42") (name "Net-(C47-Pad+)") (class "Default")
      (node (ref "C47") (pin "+") (pinfunction "+_+") (pintype "passive"))
      (node (ref "R38") (pin "1") (pinfunction "1_1") (pintype "passive"))
      (node (ref "R42") (pin "1") (pinfunction "1_1") (pintype "passive"))
    )
    (net (code "43") (name "Net-(C47-Pad-)") (class "Default")
      (node (ref "C47") (pin "-") (pinfunction "-_-") (pintype "passive"))
      (node (ref "R52") (pin "1") (pinfunction "1_1") (pintype "passive"))
      (node (ref "X3") (pin "3") (pinfunction "3_3") (pintype "passive"))
    )
    (net (code "44") (name "Net-(C48-Pad+)") (class "Default")
      (node (ref "C48") (pin "+") (pinfunction "+_+") (pintype "passive"))
      (node (ref "R46") (pin "1") (pinfunction "1_1") (pintype "passive"))
      (node (ref "R50") (pin "1") (pinfunction "1_1") (pintype "passive"))
    )
    (net (code "45") (name "Net-(C48-Pad-)") (class "Default")
      (node (ref "C48") (pin "-") (pinfunction "-_-") (pintype "passive"))
      (node (ref "R51") (pin "1") (pinfunction "1_1") (pintype "passive"))
      (node (ref "X3") (pin "2") (pinfunction "2_2") (pintype "passive"))
    )
    (net (code "46") (name "Net-(IC1A-G)") (class "Default")
      (node (ref "IC1") (pin "1") (pinfunction "G_1") (pintype "input"))
      (node (ref "IC8") (pin "19") (pinfunction "P=Q_19") (pintype "output"))
    )
    (net (code "47") (name "Net-(IC1A-Y0)") (class "Default")
      (node (ref "IC1") (pin "4") (pinfunction "Y0_4") (pintype "output"))
      (node (ref "U$1") (pin "8") (pinfunction "/CS_8") (pintype "bidirectional"))
    )
    (net (code "48") (name "Net-(IC1A-Y1)") (class "Default")
      (node (ref "IC1") (pin "5") (pinfunction "Y1_5") (pintype "output"))
      (node (ref "U$2") (pin "8") (pinfunction "/CS_8") (pintype "bidirectional"))
    )
    (net (code "49") (name "Net-(IC1B-A)") (class "Default")
      (node (ref "IC1") (pin "13") (pinfunction "B_13") (pintype "input"))
      (node (ref "IC1") (pin "14") (pinfunction "A_14") (pintype "input"))
      (node (ref "IC1") (pin "15") (pinfunction "G_15") (pintype "input"))
      (node (ref "R17") (pin "1") (pinfunction "1_1") (pintype "passive"))
    )
    (net (code "50") (name "Net-(IC3A-+IN)") (class "Default")
      (node (ref "IC3") (pin "1") (pinfunction "+IN_1") (pintype "input"))
      (node (ref "R36") (pin "1") (pinfunction "1_1") (pintype "passive"))
    )
    (net (code "51") (name "Net-(IC3A--IN)") (class "Default")
      (node (ref "IC3") (pin "6") (pinfunction "-IN_6") (pintype "input"))
      (node (ref "R35") (pin "1") (pinfunction "1_1") (pintype "passive"))
      (node (ref "R37") (pin "2") (pinfunction "2_2") (pintype "passive"))
    )
    (net (code "52") (name "Net-(IC3A-OUT)") (class "Default")
      (node (ref "IC3") (pin "5") (pinfunction "OUT_5") (pintype "output"))
      (node (ref "R37") (pin "1") (pinfunction "1_1") (pintype "passive"))
      (node (ref "R38") (pin "2") (pinfunction "2_2") (pintype "passive"))
    )
    (net (code "53") (name "Net-(IC3B-+IN)") (class "Default")
      (node (ref "IC3") (pin "2") (pinfunction "+IN_2") (pintype "input"))
      (node (ref "R40") (pin "1") (pinfunction "1_1") (pintype "passive"))
    )
    (net (code "54") (name "Net-(IC3B--IN)") (class "Default")
      (node (ref "IC3") (pin "3") (pinfunction "-IN_3") (pintype "input"))
      (node (ref "R39") (pin "1") (pinfunction "1_1") (pintype "passive"))
      (node (ref "R41") (pin "2") (pinfunction "2_2") (pintype "passive"))
    )
    (net (code "55") (name "Net-(IC3B-OUT)") (class "Default")
      (node (ref "IC3") (pin "4") (pinfunction "OUT_4") (pintype "output"))
      (node (ref "R41") (pin "1") (pinfunction "1_1") (pintype "passive"))
      (node (ref "R42") (pin "2") (pinfunction "2_2") (pintype "passive"))
    )
    (net (code "56") (name "Net-(IC3C-+IN)") (class "Default")
      (node (ref "IC3") (pin "13") (pinfunction "+IN_13") (pintype "input"))
      (node (ref "R44") (pin "1") (pinfunction "1_1") (pintype "passive"))
    )
    (net (code "57") (name "Net-(IC3C--IN)") (class "Default")
      (node (ref "IC3") (pin "8") (pinfunction "-IN_8") (pintype "input"))
      (node (ref "R43") (pin "1") (pinfunction "1_1") (pintype "passive"))
      (node (ref "R45") (pin "2") (pinfunction "2_2") (pintype "passive"))
    )
    (net (code "58") (name "Net-(IC3C-OUT)") (class "Default")
      (node (ref "IC3") (pin "9") (pinfunction "OUT_9") (pintype "output"))
      (node (ref "R45") (pin "1") (pinfunction "1_1") (pintype "passive"))
      (node (ref "R46") (pin "2") (pinfunction "2_2") (pintype "passive"))
    )
    (net (code "59") (name "Net-(IC3D-+IN)") (class "Default")
      (node (ref "IC3") (pin "12") (pinfunction "+IN_12") (pintype "input"))
      (node (ref "R48") (pin "1") (pinfunction "1_1") (pintype "passive"))
    )
    (net (code "60") (name "Net-(IC3D--IN)") (class "Default")
      (node (ref "IC3") (pin "11") (pinfunction "-IN_11") (pintype "input"))
      (node (ref "R47") (pin "1") (pinfunction "1_1") (pintype "passive"))
      (node (ref "R49") (pin "2") (pinfunction "2_2") (pintype "passive"))
    )
    (net (code "61") (name "Net-(IC3D-OUT)") (class "Default")
      (node (ref "IC3") (pin "10") (pinfunction "OUT_10") (pintype "output"))
      (node (ref "R49") (pin "1") (pinfunction "1_1") (pintype "passive"))
      (node (ref "R50") (pin "2") (pinfunction "2_2") (pintype "passive"))
    )
    (net (code "62") (name "Net-(JP2-Pad2)") (class "Default")
      (node (ref "JP2") (pin "2") (pinfunction "2_2") (pintype "passive"))
      (node (ref "R5") (pin "2") (pinfunction "2_2") (pintype "passive"))
    )
    (net (code "63") (name "Net-(JP3-Pad2)") (class "Default")
      (node (ref "JP3") (pin "2") (pinfunction "2_2") (pintype "passive"))
      (node (ref "R6") (pin "2") (pinfunction "2_2") (pintype "passive"))
    )
    (net (code "64") (name "Net-(JP5-Pad1)") (class "Default")
      (node (ref "JP5") (pin "1") (pinfunction "1_1") (pintype "passive"))
      (node (ref "R2") (pin "1") (pinfunction "1_1") (pintype "passive"))
    )
    (net (code "65") (name "Net-(JP6-Pad1)") (class "Default")
      (node (ref "JP6") (pin "1") (pinfunction "1_1") (pintype "passive"))
      (node (ref "R1") (pin "1") (pinfunction "1_1") (pintype "passive"))
    )
    (net (code "66") (name "Net-(JP7-Pad1)") (class "Default")
      (node (ref "JP7") (pin "1") (pinfunction "1_1") (pintype "passive"))
      (node (ref "R4") (pin "2") (pinfunction "2_2") (pintype "passive"))
    )
    (net (code "67") (name "Net-(JP8-Pad1)") (class "Default")
      (node (ref "JP8") (pin "1") (pinfunction "1_1") (pintype "passive"))
      (node (ref "R3") (pin "2") (pinfunction "2_2") (pintype "passive"))
    )
    (net (code "68") (name "Net-(T1-B)") (class "Default")
      (node (ref "C27") (pin "2") (pinfunction "2_2") (pintype "passive"))
      (node (ref "C30") (pin "2") (pinfunction "2_2") (pintype "passive"))
      (node (ref "R7") (pin "1") (pinfunction "1_1") (pintype "passive"))
      (node (ref "T1") (pin "2") (pinfunction "B_2") (pintype "passive"))
    )
    (net (code "69") (name "Net-(T1-E)") (class "Default")
      (node (ref "C23") (pin "+") (pinfunction "+_+") (pintype "passive"))
      (node (ref "C30") (pin "1") (pinfunction "1_1") (pintype "passive"))
      (node (ref "C31") (pin "2") (pinfunction "2_2") (pintype "passive"))
      (node (ref "JP4") (pin "3") (pinfunction "3_3") (pintype "passive"))
      (node (ref "R9") (pin "1") (pinfunction "1_1") (pintype "passive"))
      (node (ref "T1") (pin "1") (pinfunction "E_1") (pintype "passive"))
    )
    (net (code "70") (name "Net-(T2-B)") (class "Default")
      (node (ref "C28") (pin "2") (pinfunction "2_2") (pintype "passive"))
      (node (ref "C29") (pin "2") (pinfunction "2_2") (pintype "passive"))
      (node (ref "R8") (pin "1") (pinfunction "1_1") (pintype "passive"))
      (node (ref "T2") (pin "2") (pinfunction "B_2") (pintype "passive"))
    )
    (net (code "71") (name "Net-(T2-E)") (class "Default")
      (node (ref "C29") (pin "1") (pinfunction "1_1") (pintype "passive"))
      (node (ref "C32") (pin "2") (pinfunction "2_2") (pintype "passive"))
      (node (ref "JP4") (pin "1") (pinfunction "1_1") (pintype "passive"))
      (node (ref "R10") (pin "1") (pinfunction "1_1") (pintype "passive"))
      (node (ref "T2") (pin "1") (pinfunction "E_1") (pintype "passive"))
    )
    (net (code "72") (name "Net-(U$1-CAP1A)") (class "Default")
      (node (ref "C8") (pin "1") (pinfunction "1_1") (pintype "passive"))
      (node (ref "U$1") (pin "1") (pinfunction "CAP1A_1") (pintype "bidirectional"))
    )
    (net (code "73") (name "Net-(U$1-CAP1B)") (class "Default")
      (node (ref "C8") (pin "2") (pinfunction "2_2") (pintype "passive"))
      (node (ref "U$1") (pin "2") (pinfunction "CAP1B_2") (pintype "bidirectional"))
    )
    (net (code "74") (name "Net-(U$1-CAP2A)") (class "Default")
      (node (ref "C11") (pin "1") (pinfunction "1_1") (pintype "passive"))
      (node (ref "U$1") (pin "3") (pinfunction "CAP2A_3") (pintype "bidirectional"))
    )
    (net (code "75") (name "Net-(U$1-CAP2B)") (class "Default")
      (node (ref "C11") (pin "2") (pinfunction "2_2") (pintype "passive"))
      (node (ref "U$1") (pin "4") (pinfunction "CAP2B_4") (pintype "bidirectional"))
    )
    (net (code "76") (name "Net-(U$1-EXTIN)") (class "Default")
      (node (ref "C10") (pin "-") (pinfunction "-_-") (pintype "passive"))
      (node (ref "U$1") (pin "26") (pinfunction "EXTIN_26") (pintype "bidirectional"))
    )
    (net (code "77") (name "Net-(U$1-POTX)") (class "Default")
      (node (ref "C18") (pin "2") (pinfunction "2_2") (pintype "passive"))
      (node (ref "JP5") (pin "2") (pinfunction "2_2") (pintype "passive"))
      (node (ref "U$1") (pin "24") (pinfunction "POTX_24") (pintype "bidirectional"))
    )
    (net (code "78") (name "Net-(U$1-POTY)") (class "Default")
      (node (ref "C17") (pin "2") (pinfunction "2_2") (pintype "passive"))
      (node (ref "JP6") (pin "2") (pinfunction "2_2") (pintype "passive"))
      (node (ref "U$1") (pin "23") (pinfunction "POTY_23") (pintype "bidirectional"))
    )
    (net (code "79") (name "Net-(U$2-CAP1A)") (class "Default")
      (node (ref "C15") (pin "1") (pinfunction "1_1") (pintype "passive"))
      (node (ref "U$2") (pin "1") (pinfunction "CAP1A_1") (pintype "bidirectional"))
    )
    (net (code "80") (name "Net-(U$2-CAP1B)") (class "Default")
      (node (ref "C15") (pin "2") (pinfunction "2_2") (pintype "passive"))
      (node (ref "U$2") (pin "2") (pinfunction "CAP1B_2") (pintype "bidirectional"))
    )
    (net (code "81") (name "Net-(U$2-CAP2A)") (class "Default")
      (node (ref "C16") (pin "1") (pinfunction "1_1") (pintype "passive"))
      (node (ref "U$2") (pin "3") (pinfunction "CAP2A_3") (pintype "bidirectional"))
    )
    (net (code "82") (name "Net-(U$2-CAP2B)") (class "Default")
      (node (ref "C16") (pin "2") (pinfunction "2_2") (pintype "passive"))
      (node (ref "U$2") (pin "4") (pinfunction "CAP2B_4") (pintype "bidirectional"))
    )
    (net (code "83") (name "Net-(U$2-EXTIN)") (class "Default")
      (node (ref "C6") (pin "-") (pinfunction "-_-") (pintype "passive"))
      (node (ref "U$2") (pin "26") (pinfunction "EXTIN_26") (pintype "bidirectional"))
    )
    (net (code "84") (name "Net-(U$2-POTX)") (class "Default")
      (node (ref "C22") (pin "2") (pinfunction "2_2") (pintype "passive"))
      (node (ref "JP7") (pin "2") (pinfunction "2_2") (pintype "passive"))
      (node (ref "U$2") (pin "24") (pinfunction "POTX_24") (pintype "bidirectional"))
    )
    (net (code "85") (name "Net-(U$2-POTY)") (class "Default")
      (node (ref "C19") (pin "2") (pinfunction "2_2") (pintype "passive"))
      (node (ref "JP8") (pin "2") (pinfunction "2_2") (pintype "passive"))
      (node (ref "U$2") (pin "23") (pinfunction "POTY_23") (pintype "bidirectional"))
    )
    (net (code "86") (name "Net-(U$3-COMPARATOR)") (class "Default")
      (node (ref "R13") (pin "2") (pinfunction "2_2") (pintype "passive"))
      (node (ref "R16") (pin "1") (pinfunction "1_1") (pintype "passive"))
      (node (ref "U$3") (pin "5") (pinfunction "COMPARATOR_5") (pintype "bidirectional"))
    )
    (net (code "87") (name "Net-(U$3-DCOLLECTOR)") (class "Default")
      (node (ref "R15") (pin "1") (pinfunction "1_1") (pintype "passive"))
      (node (ref "U$3") (pin "8") (pinfunction "DCOLLECTOR_8") (pintype "bidirectional"))
    )
    (net (code "88") (name "Net-(U$3-IPK)") (class "Default")
      (node (ref "L4") (pin "2") (pinfunction "2_2") (pintype "passive"))
      (node (ref "R14") (pin "2") (pinfunction "2_2") (pintype "passive"))
      (node (ref "R15") (pin "2") (pinfunction "2_2") (pintype "passive"))
      (node (ref "U$3") (pin "7") (pinfunction "IPK_7") (pintype "bidirectional"))
    )
    (net (code "89") (name "Net-(U$3-SCOLLECTOR)") (class "Default")
      (node (ref "D2") (pin "A") (pinfunction "A_A") (pintype "passive"))
      (node (ref "L4") (pin "1") (pinfunction "1_1") (pintype "passive"))
      (node (ref "U$3") (pin "1") (pinfunction "SCOLLECTOR_1") (pintype "bidirectional"))
    )
    (net (code "90") (name "Net-(U$3-TCAP)") (class "Default")
      (node (ref "C36") (pin "1") (pinfunction "1_1") (pintype "passive"))
      (node (ref "U$3") (pin "3") (pinfunction "TCAP_3") (pintype "bidirectional"))
    )
    (net (code "91") (name "PHI2") (class "Default")
      (node (ref "P1") (pin "C26") (pinfunction "PHI2_C26") (pintype "bidirectional"))
      (node (ref "U$1") (pin "6") (pinfunction "PHI2_6") (pintype "bidirectional"))
      (node (ref "U$2") (pin "6") (pinfunction "PHI2_6") (pintype "bidirectional"))
    )
    (net (code "92") (name "R{slash}-W") (class "Default")
      (node (ref "P1") (pin "C25") (pinfunction "R/-W_C25") (pintype "bidirectional"))
      (node (ref "U$1") (pin "7") (pinfunction "R/-W_7") (pintype "bidirectional"))
      (node (ref "U$2") (pin "7") (pinfunction "R/-W_7") (pintype "bidirectional"))
    )
    (net (code "93") (name "SIDLEFT") (class "Default")
      (node (ref "C46") (pin "+") (pinfunction "+_+") (pintype "passive"))
      (node (ref "JP2") (pin "1") (pinfunction "1_1") (pintype "passive"))
      (node (ref "R7") (pin "2") (pinfunction "2_2") (pintype "passive"))
      (node (ref "U$1") (pin "27") (pinfunction "AUDIO_OUT_27") (pintype "bidirectional"))
    )
    (net (code "94") (name "SIDRIGHT") (class "Default")
      (node (ref "C44") (pin "+") (pinfunction "+_+") (pintype "passive"))
      (node (ref "JP3") (pin "1") (pinfunction "1_1") (pintype "passive"))
      (node (ref "R8") (pin "2") (pinfunction "2_2") (pintype "passive"))
      (node (ref "U$2") (pin "27") (pinfunction "AUDIO_OUT_27") (pintype "bidirectional"))
    )
    (net (code "95") (name "VCC") (class "Default")
      (node (ref "C1") (pin "+") (pinfunction "+_+") (pintype "passive"))
      (node (ref "C2") (pin "1") (pinfunction "1_1") (pintype "passive"))
      (node (ref "C3") (pin "1") (pinfunction "1_1") (pintype "passive"))
      (node (ref "C33") (pin "+") (pinfunction "+_+") (pintype "passive"))
      (node (ref "C4") (pin "1") (pinfunction "1_1") (pintype "passive"))
      (node (ref "C5") (pin "1") (pinfunction "1_1") (pintype "passive"))
      (node (ref "C7") (pin "1") (pinfunction "1_1") (pintype "passive"))
      (node (ref "C9") (pin "1") (pinfunction "1_1") (pintype "passive"))
      (node (ref "IC3") (pin "14") (pinfunction "V+_14") (pintype "power_in"))
      (node (ref "IC8") (pin "12") (pinfunction "Q7_12") (pintype "input"))
      (node (ref "IC8") (pin "15") (pinfunction "P3_15") (pintype "input"))
      (node (ref "IC8") (pin "16") (pinfunction "Q3_16") (pintype "input"))
      (node (ref "IC8") (pin "18") (pinfunction "Q1_18") (pintype "input"))
      (node (ref "IC8") (pin "2") (pinfunction "P0_2") (pintype "input"))
      (node (ref "IC8") (pin "3") (pinfunction "Q0_3") (pintype "input"))
      (node (ref "IC8") (pin "5") (pinfunction "Q2_5") (pintype "input"))
      (node (ref "JP5") (pin "3") (pinfunction "3_3") (pintype "passive"))
      (node (ref "JP6") (pin "3") (pinfunction "3_3") (pintype "passive"))
      (node (ref "JP7") (pin "3") (pinfunction "3_3") (pintype "passive"))
      (node (ref "JP8") (pin "3") (pinfunction "3_3") (pintype "passive"))
      (node (ref "P1") (pin "C2") (pinfunction "VCC_C2") (pintype "bidirectional"))
      (node (ref "P1") (pin "C3") (pinfunction "VCC2_C3") (pintype "bidirectional"))
      (node (ref "R1") (pin "2") (pinfunction "2_2") (pintype "passive"))
      (node (ref "R14") (pin "1") (pinfunction "1_1") (pintype "passive"))
      (node (ref "R17") (pin "2") (pinfunction "2_2") (pintype "passive"))
      (node (ref "R2") (pin "2") (pinfunction "2_2") (pintype "passive"))
      (node (ref "R3") (pin "1") (pinfunction "1_1") (pintype "passive"))
      (node (ref "R4") (pin "1") (pinfunction "1_1") (pintype "passive"))
      (node (ref "U$1") (pin "25") (pinfunction "VCC_25") (pintype "bidirectional"))
      (node (ref "U$2") (pin "25") (pinfunction "VCC_25") (pintype "bidirectional"))
      (node (ref "U$3") (pin "6") (pinfunction "VCC_6") (pintype "bidirectional"))
    )
    (net (code "96") (name "VDD") (class "Default")
      (node (ref "C34") (pin "+") (pinfunction "+_+") (pintype "passive"))
      (node (ref "L2") (pin "2") (pinfunction "2_2") (pintype "passive"))
      (node (ref "T1") (pin "3") (pinfunction "C_3") (pintype "passive"))
      (node (ref "T2") (pin "3") (pinfunction "C_3") (pintype "passive"))
      (node (ref "U$1") (pin "28") (pinfunction "VDD_28") (pintype "bidirectional"))
      (node (ref "U$2") (pin "28") (pinfunction "VDD_28") (pintype "bidirectional"))
    )
    (net (code "97") (name "unconnected-(IC1A-Y2-Pad6)") (class "Default")
      (node (ref "IC1") (pin "6") (pinfunction "Y2_6") (pintype "output"))
    )
    (net (code "98") (name "unconnected-(IC1A-Y3-Pad7)") (class "Default")
      (node (ref "IC1") (pin "7") (pinfunction "Y3_7") (pintype "output"))
    )
    (net (code "99") (name "unconnected-(IC1B-Y0-Pad12)") (class "Default")
      (node (ref "IC1") (pin "12") (pinfunction "Y0_12") (pintype "output"))
    )
    (net (code "100") (name "unconnected-(IC1B-Y1-Pad11)") (class "Default")
      (node (ref "IC1") (pin "11") (pinfunction "Y1_11") (pintype "output"))
    )
    (net (code "101") (name "unconnected-(IC1B-Y2-Pad10)") (class "Default")
      (node (ref "IC1") (pin "10") (pinfunction "Y2_10") (pintype "output"))
    )
    (net (code "102") (name "unconnected-(IC1B-Y3-Pad9)") (class "Default")
      (node (ref "IC1") (pin "9") (pinfunction "Y3_9") (pintype "output"))
    )
    (net (code "103") (name "unconnected-(P1-2PHI2-PadC29)") (class "Default")
      (node (ref "P1") (pin "C29") (pinfunction "2PHI2_C29") (pintype "bidirectional"))
    )
    (net (code "104") (name "unconnected-(P1-8PHI2-PadC31)") (class "Default")
      (node (ref "P1") (pin "C31") (pinfunction "8PHI2_C31") (pintype "bidirectional"))
    )
    (net (code "105") (name "unconnected-(P1-16MHZ-PadC30)") (class "Default")
      (node (ref "P1") (pin "C30") (pinfunction "16MHZ_C30") (pintype "bidirectional"))
    )
    (net (code "106") (name "unconnected-(P1-50HZ-PadA3)") (class "Default")
      (node (ref "P1") (pin "A3") (pinfunction "50HZ_A3") (pintype "bidirectional"))
    )
    (net (code "107") (name "unconnected-(P1-I2CSCL-PadA14)") (class "Default")
      (node (ref "P1") (pin "A14") (pinfunction "I2CSCL_A14") (pintype "bidirectional"))
    )
    (net (code "108") (name "unconnected-(P1-I2CSDA-PadA13)") (class "Default")
      (node (ref "P1") (pin "A13") (pinfunction "I2CSDA_A13") (pintype "bidirectional"))
    )
    (net (code "109") (name "unconnected-(P1-NOEXEC-PadA10)") (class "Default")
      (node (ref "P1") (pin "A10") (pinfunction "NOEXEC_A10") (pintype "bidirectional"))
    )
    (net (code "110") (name "unconnected-(P1-NOTMAPD-PadA11)") (class "Default")
      (node (ref "P1") (pin "A11") (pinfunction "NOTMAPD_A11") (pintype "bidirectional"))
    )
    (net (code "111") (name "unconnected-(P1-PHI0-PadC28)") (class "Default")
      (node (ref "P1") (pin "C28") (pinfunction "PHI0_C28") (pintype "bidirectional"))
    )
    (net (code "112") (name "unconnected-(P1-PHI1-PadC27)") (class "Default")
      (node (ref "P1") (pin "C27") (pinfunction "PHI1_C27") (pintype "bidirectional"))
    )
    (net (code "113") (name "unconnected-(P1-RDY-PadA26)") (class "Default")
      (node (ref "P1") (pin "A26") (pinfunction "RDY_A26") (pintype "bidirectional"))
    )
    (net (code "114") (name "unconnected-(P1-SYNC-PadC24)") (class "Default")
      (node (ref "P1") (pin "C24") (pinfunction "SYNC_C24") (pintype "bidirectional"))
    )
    (net (code "115") (name "unconnected-(P1-VBUF-PadA2)") (class "Default")
      (node (ref "P1") (pin "A2") (pinfunction "VBUF_A2") (pintype "bidirectional"))
    )
    (net (code "116") (name "unconnected-(P1-VCC33-PadA9)") (class "Default")
      (node (ref "P1") (pin "A9") (pinfunction "VCC33_A9") (pintype "bidirectional"))
    )
    (net (code "117") (name "unconnected-(P1-WPROT-PadA12)") (class "Default")
      (node (ref "P1") (pin "A12") (pinfunction "WPROT_A12") (pintype "bidirectional"))
    )
    (net (code "118") (name "unconnected-(P1-{slash}BE-PadA8)") (class "Default")
      (node (ref "P1") (pin "A8") (pinfunction "/BE_A8") (pintype "bidirectional"))
    )
    (net (code "119") (name "unconnected-(P1-{slash}EXTIO-PadA5)") (class "Default")
      (node (ref "P1") (pin "A5") (pinfunction "/EXTIO_A5") (pintype "bidirectional"))
    )
    (net (code "120") (name "unconnected-(P1-{slash}IOINH-PadA4)") (class "Default")
      (node (ref "P1") (pin "A4") (pinfunction "/IOINH_A4") (pintype "bidirectional"))
    )
    (net (code "121") (name "unconnected-(P1-{slash}IRQ-PadA24)") (class "Default")
      (node (ref "P1") (pin "A24") (pinfunction "/IRQ_A24") (pintype "bidirectional"))
    )
    (net (code "122") (name "unconnected-(P1-{slash}MEMSEL-PadA6)") (class "Default")
      (node (ref "P1") (pin "A6") (pinfunction "/MEMSEL_A6") (pintype "bidirectional"))
    )
    (net (code "123") (name "unconnected-(P1-{slash}NMI-PadA23)") (class "Default")
      (node (ref "P1") (pin "A23") (pinfunction "/NMI_A23") (pintype "bidirectional"))
    )
    (net (code "124") (name "unconnected-(P1-{slash}SO-PadA25)") (class "Default")
      (node (ref "P1") (pin "A25") (pinfunction "/SO_A25") (pintype "bidirectional"))
    )
    (net (code "125") (name "unconnected-(X1-Pad4)") (class "Default")
      (node (ref "X1") (pin "4") (pinfunction "4_4") (pintype "passive"))
    )
    (net (code "126") (name "unconnected-(X1-Pad5)") (class "Default")
      (node (ref "X1") (pin "5") (pinfunction "5_5") (pintype "passive"))
    )
    (net (code "127") (name "unconnected-(X3-Pad4)") (class "Default")
      (node (ref "X3") (pin "4") (pinfunction "4_4") (pintype "passive"))
    )
    (net (code "128") (name "unconnected-(X3-Pad5)") (class "Default")
      (node (ref "X3") (pin "5") (pinfunction "5_5") (pintype "passive"))
    )
    (net (code "129") (name "{slash}IOSEL") (class "Default")
      (node (ref "IC8") (pin "1") (pinfunction "G_1") (pintype "input"))
      (node (ref "P1") (pin "A7") (pinfunction "/IOSEL_A7") (pintype "bidirectional"))
    )
    (net (code "130") (name "{slash}RES") (class "Default")
      (node (ref "P1") (pin "A27") (pinfunction "/RES_A27") (pintype "bidirectional"))
      (node (ref "U$1") (pin "5") (pinfunction "/RES_5") (pintype "bidirectional"))
      (node (ref "U$2") (pin "5") (pinfunction "/RES_5") (pintype "bidirectional"))
    )
  )
)
